# wclock.net
KiCad netlist of a schematic drawn in EAGLE
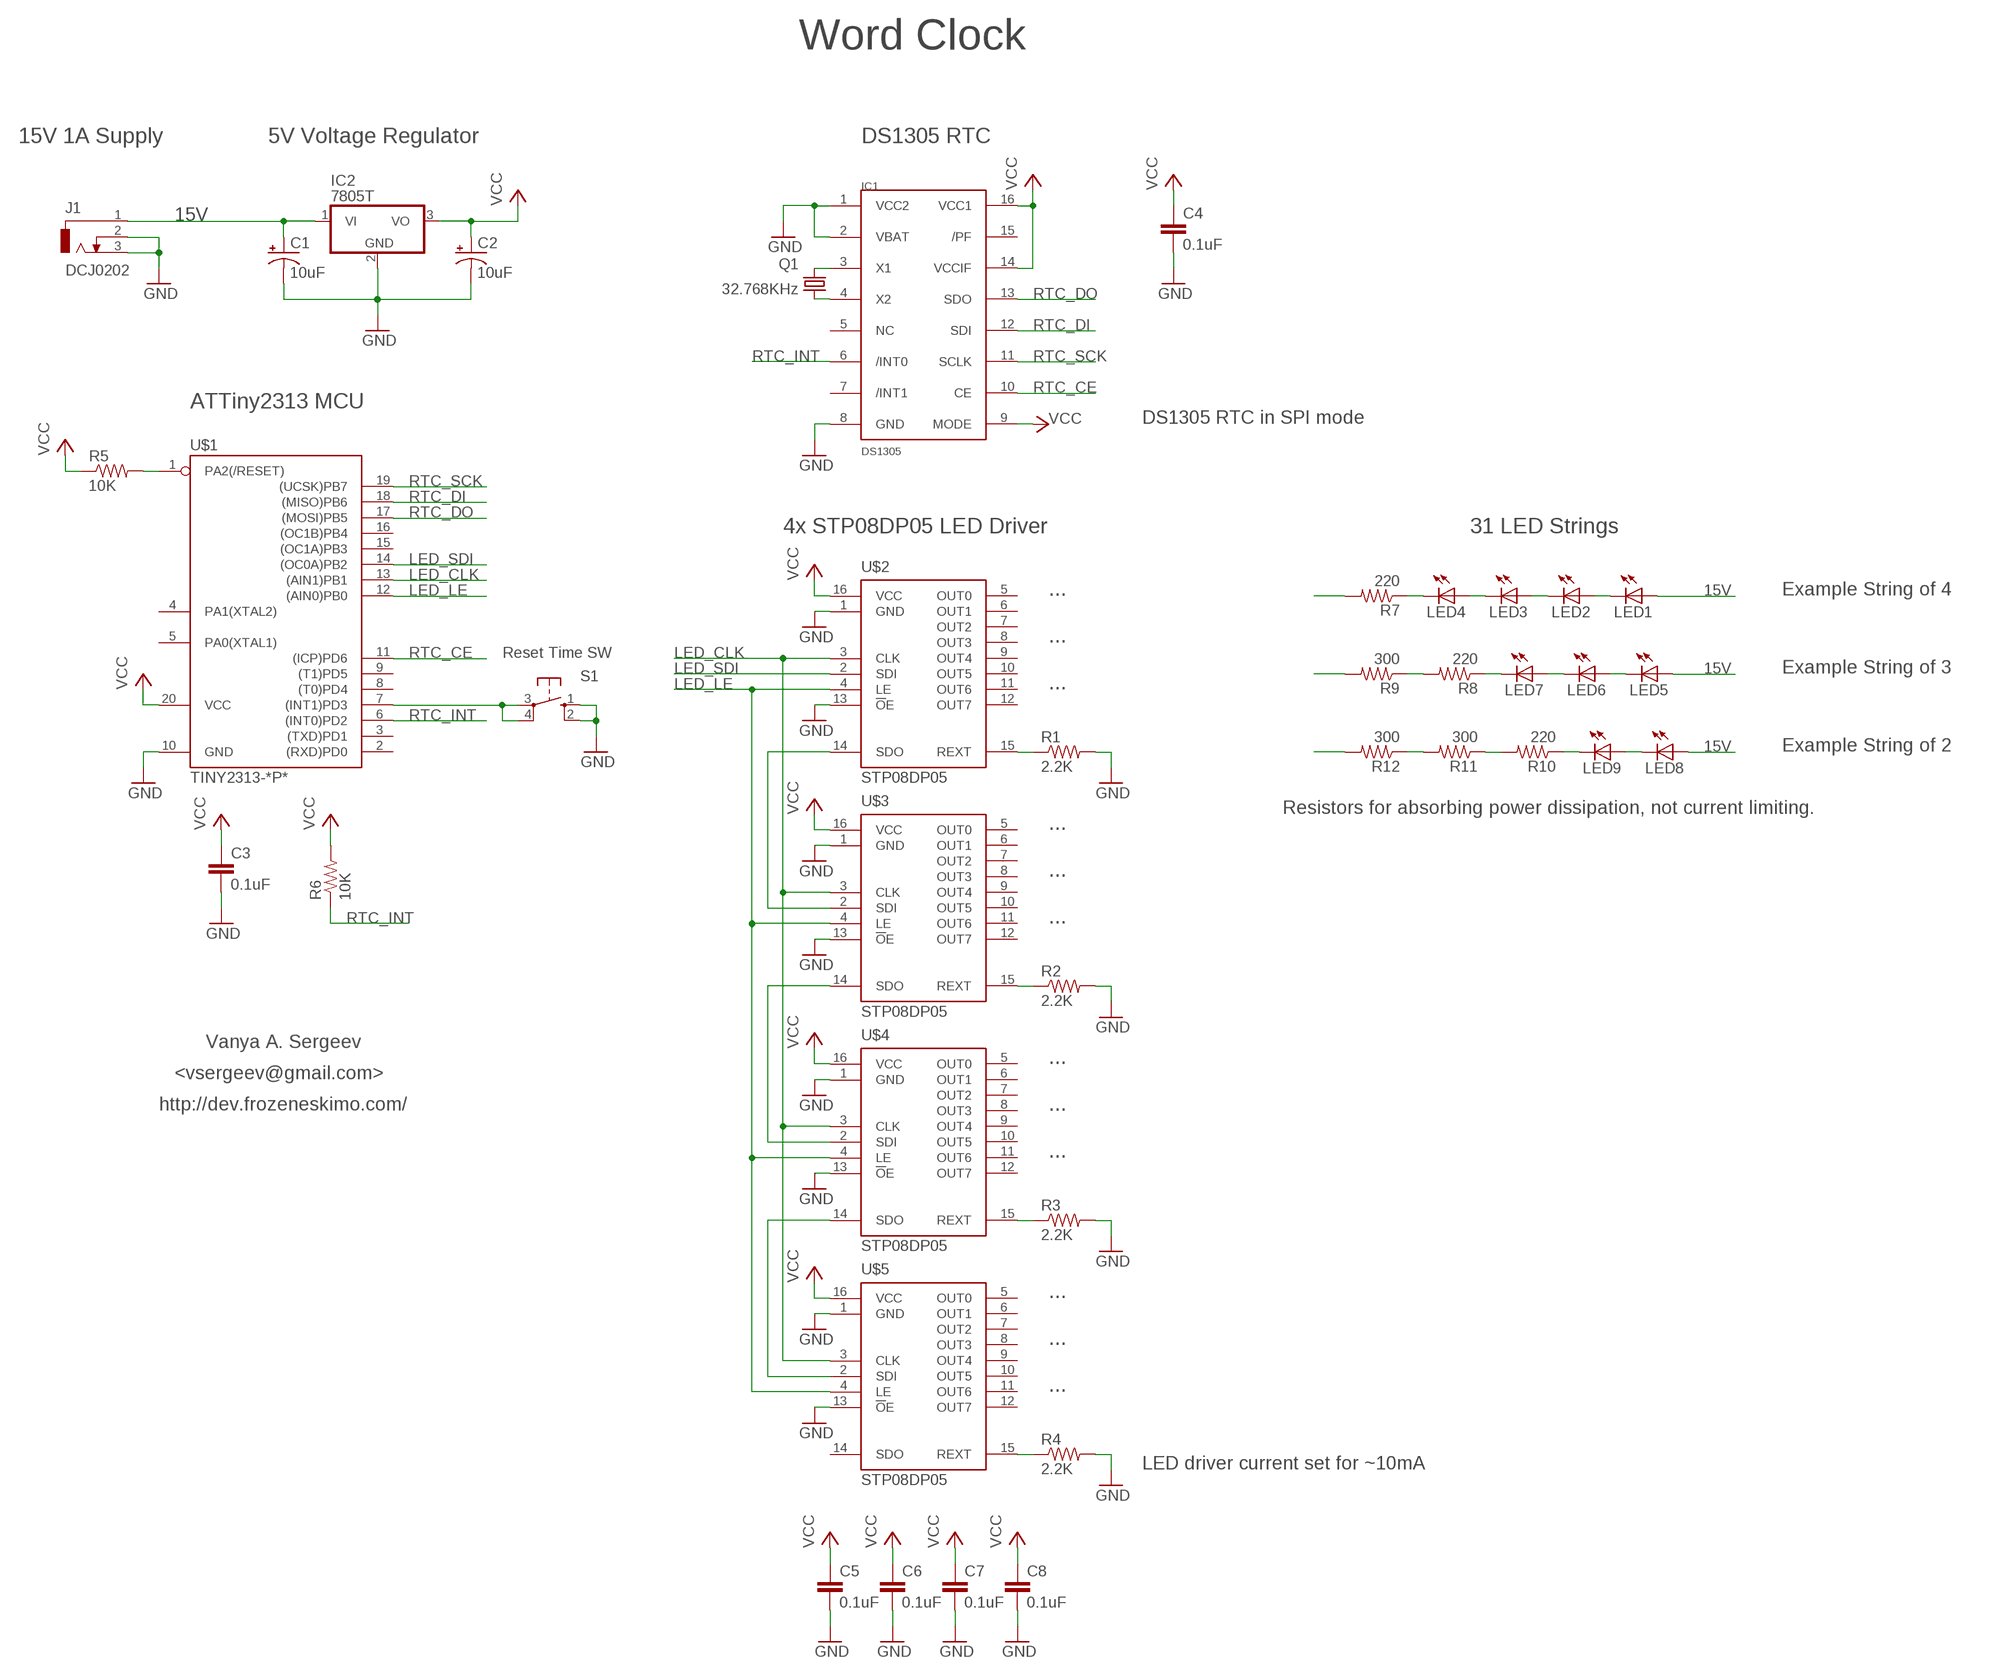
[diagram p0: schematic, sheet 1]

(export (version "E")
  (design (tool "Eeschema 10.0.6"))
  (components
    (comp (ref "C1")
      (value "10uF")
      (footprint "eagle-import:E2,5-5")
      (libsource (lib "eagle-import") (part "CPOL-USE2.5-5"))
    )
    (comp (ref "C2")
      (value "10uF")
      (footprint "eagle-import:E2,5-5")
      (libsource (lib "eagle-import") (part "CPOL-USE2.5-5"))
    )
    (comp (ref "C3")
      (value "0.1uF")
      (footprint "eagle-import:C025-025X050")
      (libsource (lib "eagle-import") (part "C-EU025-025X050"))
    )
    (comp (ref "C4")
      (value "0.1uF")
      (footprint "eagle-import:C025-025X050")
      (libsource (lib "eagle-import") (part "C-EU025-025X050"))
    )
    (comp (ref "C5")
      (value "0.1uF")
      (footprint "eagle-import:C025-025X050")
      (libsource (lib "eagle-import") (part "C-EU025-025X050"))
    )
    (comp (ref "C6")
      (value "0.1uF")
      (footprint "eagle-import:C025-025X050")
      (libsource (lib "eagle-import") (part "C-EU025-025X050"))
    )
    (comp (ref "C7")
      (value "0.1uF")
      (footprint "eagle-import:C025-025X050")
      (libsource (lib "eagle-import") (part "C-EU025-025X050"))
    )
    (comp (ref "C8")
      (value "0.1uF")
      (footprint "eagle-import:C025-025X050")
      (libsource (lib "eagle-import") (part "C-EU025-025X050"))
    )
    (comp (ref "IC1")
      (value "DS1305")
      (footprint "eagle-import:DIL16")
      (libsource (lib "eagle-import") (part "DS1305"))
    )
    (comp (ref "IC2")
      (value "7805T")
      (footprint "eagle-import:TO220H")
      (libsource (lib "eagle-import") (part "78T05"))
    )
    (comp (ref "J1")
      (value "DCJ0202")
      (footprint "eagle-import:DCJ0202")
      (libsource (lib "eagle-import") (part "DCJ0202"))
    )
    (comp (ref "LED1")
      (value "LED5MM")
      (footprint "eagle-import:LED5MM")
      (libsource (lib "eagle-import") (part "LED5MM"))
    )
    (comp (ref "LED2")
      (value "LED5MM")
      (footprint "eagle-import:LED5MM")
      (libsource (lib "eagle-import") (part "LED5MM"))
    )
    (comp (ref "LED3")
      (value "LED5MM")
      (footprint "eagle-import:LED5MM")
      (libsource (lib "eagle-import") (part "LED5MM"))
    )
    (comp (ref "LED4")
      (value "LED5MM")
      (footprint "eagle-import:LED5MM")
      (libsource (lib "eagle-import") (part "LED5MM"))
    )
    (comp (ref "LED5")
      (value "LED5MM")
      (footprint "eagle-import:LED5MM")
      (libsource (lib "eagle-import") (part "LED5MM"))
    )
    (comp (ref "LED6")
      (value "LED5MM")
      (footprint "eagle-import:LED5MM")
      (libsource (lib "eagle-import") (part "LED5MM"))
    )
    (comp (ref "LED7")
      (value "LED5MM")
      (footprint "eagle-import:LED5MM")
      (libsource (lib "eagle-import") (part "LED5MM"))
    )
    (comp (ref "LED8")
      (value "LED5MM")
      (footprint "eagle-import:LED5MM")
      (libsource (lib "eagle-import") (part "LED5MM"))
    )
    (comp (ref "LED9")
      (value "LED5MM")
      (footprint "eagle-import:LED5MM")
      (libsource (lib "eagle-import") (part "LED5MM"))
    )
    (comp (ref "Q1")
      (value "32.768KHz")
      (footprint "eagle-import:TC26V")
      (libsource (lib "eagle-import") (part "CRYSTALTC26V"))
    )
    (comp (ref "R1")
      (value "2.2K")
      (footprint "eagle-import:0207_10")
      (libsource (lib "eagle-import") (part "R-US_0207/10"))
    )
    (comp (ref "R2")
      (value "2.2K")
      (footprint "eagle-import:0207_10")
      (libsource (lib "eagle-import") (part "R-US_0207/10"))
    )
    (comp (ref "R3")
      (value "2.2K")
      (footprint "eagle-import:0207_10")
      (libsource (lib "eagle-import") (part "R-US_0207/10"))
    )
    (comp (ref "R4")
      (value "2.2K")
      (footprint "eagle-import:0207_10")
      (libsource (lib "eagle-import") (part "R-US_0207/10"))
    )
    (comp (ref "R5")
      (value "10K")
      (footprint "eagle-import:0207_10")
      (libsource (lib "eagle-import") (part "R-US_0207/10"))
    )
    (comp (ref "R6")
      (value "10K")
      (footprint "eagle-import:0207_10")
      (libsource (lib "eagle-import") (part "R-US_0207/10"))
    )
    (comp (ref "R7")
      (value "220")
      (footprint "eagle-import:0207_10")
      (libsource (lib "eagle-import") (part "R-US_0207/10"))
    )
    (comp (ref "R8")
      (value "220")
      (footprint "eagle-import:0207_10")
      (libsource (lib "eagle-import") (part "R-US_0207/10"))
    )
    (comp (ref "R9")
      (value "300")
      (footprint "eagle-import:0207_10")
      (libsource (lib "eagle-import") (part "R-US_0207/10"))
    )
    (comp (ref "R10")
      (value "220")
      (footprint "eagle-import:0207_10")
      (libsource (lib "eagle-import") (part "R-US_0207/10"))
    )
    (comp (ref "R11")
      (value "300")
      (footprint "eagle-import:0207_10")
      (libsource (lib "eagle-import") (part "R-US_0207/10"))
    )
    (comp (ref "R12")
      (value "300")
      (footprint "eagle-import:0207_10")
      (libsource (lib "eagle-import") (part "R-US_0207/10"))
    )
    (comp (ref "S1")
      (value "10-XX")
      (footprint "eagle-import:B3F-10XX")
      (fields (field (name "MPN") "B3F-1000"))
      (libsource (lib "eagle-import") (part "10-XX"))
    )
    (comp (ref "U$1")
      (value "TINY2313-*P*")
      (footprint "eagle-import:DIL20")
      (libsource (lib "eagle-import") (part "TINY2313-P"))
    )
    (comp (ref "U$2")
      (value "STP08DP05")
      (footprint "eagle-import:DIL16")
      (libsource (lib "eagle-import") (part "STP08DP05"))
    )
    (comp (ref "U$3")
      (value "STP08DP05")
      (footprint "eagle-import:DIL16")
      (libsource (lib "eagle-import") (part "STP08DP05"))
    )
    (comp (ref "U$4")
      (value "STP08DP05")
      (footprint "eagle-import:DIL16")
      (libsource (lib "eagle-import") (part "STP08DP05"))
    )
    (comp (ref "U$5")
      (value "STP08DP05")
      (footprint "eagle-import:DIL16")
      (libsource (lib "eagle-import") (part "STP08DP05"))
    )
  )
  (nets
    (net (code "1") (name "/15V") (class "Default")
      (node (ref "C1") (pin "+") (pinfunction "+_+") (pintype "passive"))
      (node (ref "IC2") (pin "1") (pinfunction "VI_1") (pintype "input"))
      (node (ref "J1") (pin "1") (pinfunction "1_1") (pintype "passive"))
      (node (ref "LED1") (pin "A") (pinfunction "A_A") (pintype "passive"))
      (node (ref "LED5") (pin "A") (pinfunction "A_A") (pintype "passive"))
      (node (ref "LED8") (pin "A") (pinfunction "A_A") (pintype "passive"))
    )
    (net (code "2") (name "/LED_CLK") (class "Default")
      (node (ref "U$1") (pin "13") (pinfunction "(AIN1)PB1_13") (pintype "bidirectional"))
      (node (ref "U$2") (pin "3") (pinfunction "CLK_3") (pintype "bidirectional"))
      (node (ref "U$3") (pin "3") (pinfunction "CLK_3") (pintype "bidirectional"))
      (node (ref "U$4") (pin "3") (pinfunction "CLK_3") (pintype "bidirectional"))
      (node (ref "U$5") (pin "3") (pinfunction "CLK_3") (pintype "bidirectional"))
    )
    (net (code "3") (name "/LED_LE") (class "Default")
      (node (ref "U$1") (pin "12") (pinfunction "(AIN0)PB0_12") (pintype "bidirectional"))
      (node (ref "U$2") (pin "4") (pinfunction "LE_4") (pintype "bidirectional"))
      (node (ref "U$3") (pin "4") (pinfunction "LE_4") (pintype "bidirectional"))
      (node (ref "U$4") (pin "4") (pinfunction "LE_4") (pintype "bidirectional"))
      (node (ref "U$5") (pin "4") (pinfunction "LE_4") (pintype "bidirectional"))
    )
    (net (code "4") (name "/LED_SDI") (class "Default")
      (node (ref "U$1") (pin "14") (pinfunction "(OC0A)PB2_14") (pintype "bidirectional"))
      (node (ref "U$2") (pin "2") (pinfunction "SDI_2") (pintype "bidirectional"))
    )
    (net (code "5") (name "/RTC_CE") (class "Default")
      (node (ref "IC1") (pin "10") (pinfunction "CE_10") (pintype "input"))
      (node (ref "U$1") (pin "11") (pinfunction "(ICP)PD6_11") (pintype "bidirectional"))
    )
    (net (code "6") (name "/RTC_DI") (class "Default")
      (node (ref "IC1") (pin "12") (pinfunction "SDI_12") (pintype "input"))
      (node (ref "U$1") (pin "18") (pinfunction "(MISO)PB6_18") (pintype "bidirectional"))
    )
    (net (code "7") (name "/RTC_DO") (class "Default")
      (node (ref "IC1") (pin "13") (pinfunction "SDO_13") (pintype "output"))
      (node (ref "U$1") (pin "17") (pinfunction "(MOSI)PB5_17") (pintype "bidirectional"))
    )
    (net (code "8") (name "/RTC_INT") (class "Default")
      (node (ref "IC1") (pin "6") (pinfunction "/INT0_6") (pintype "output"))
      (node (ref "R6") (pin "1") (pinfunction "1_1") (pintype "passive"))
      (node (ref "U$1") (pin "6") (pinfunction "(INT0)PD2_6") (pintype "bidirectional"))
    )
    (net (code "9") (name "/RTC_SCK") (class "Default")
      (node (ref "IC1") (pin "11") (pinfunction "SCLK_11") (pintype "input"))
      (node (ref "U$1") (pin "19") (pinfunction "(UCSK)PB7_19") (pintype "bidirectional"))
    )
    (net (code "10") (name "GND") (class "Default")
      (node (ref "C1") (pin "-") (pinfunction "-_-") (pintype "passive"))
      (node (ref "C2") (pin "-") (pinfunction "-_-") (pintype "passive"))
      (node (ref "C3") (pin "2") (pinfunction "2_2") (pintype "passive"))
      (node (ref "C4") (pin "2") (pinfunction "2_2") (pintype "passive"))
      (node (ref "C5") (pin "2") (pinfunction "2_2") (pintype "passive"))
      (node (ref "C6") (pin "2") (pinfunction "2_2") (pintype "passive"))
      (node (ref "C7") (pin "2") (pinfunction "2_2") (pintype "passive"))
      (node (ref "C8") (pin "2") (pinfunction "2_2") (pintype "passive"))
      (node (ref "IC1") (pin "1") (pinfunction "VCC2_1") (pintype "power_in"))
      (node (ref "IC1") (pin "2") (pinfunction "VBAT_2") (pintype "power_in"))
      (node (ref "IC1") (pin "8") (pinfunction "GND_8") (pintype "power_in"))
      (node (ref "IC2") (pin "2") (pinfunction "GND_2") (pintype "passive"))
      (node (ref "J1") (pin "2") (pinfunction "2_2") (pintype "passive"))
      (node (ref "J1") (pin "3") (pinfunction "3_3") (pintype "passive"))
      (node (ref "R1") (pin "2") (pinfunction "2_2") (pintype "passive"))
      (node (ref "R2") (pin "2") (pinfunction "2_2") (pintype "passive"))
      (node (ref "R3") (pin "2") (pinfunction "2_2") (pintype "passive"))
      (node (ref "R4") (pin "2") (pinfunction "2_2") (pintype "passive"))
      (node (ref "S1") (pin "1") (pinfunction "S_1") (pintype "passive"))
      (node (ref "S1") (pin "2") (pinfunction "S1_2") (pintype "passive"))
      (node (ref "U$1") (pin "10") (pinfunction "GND_10") (pintype "power_in"))
      (node (ref "U$2") (pin "1") (pinfunction "GND_1") (pintype "power_in"))
      (node (ref "U$2") (pin "13") (pinfunction "~{O}E_13") (pintype "bidirectional"))
      (node (ref "U$3") (pin "1") (pinfunction "GND_1") (pintype "power_in"))
      (node (ref "U$3") (pin "13") (pinfunction "~{O}E_13") (pintype "bidirectional"))
      (node (ref "U$4") (pin "1") (pinfunction "GND_1") (pintype "power_in"))
      (node (ref "U$4") (pin "13") (pinfunction "~{O}E_13") (pintype "bidirectional"))
      (node (ref "U$5") (pin "1") (pinfunction "GND_1") (pintype "power_in"))
      (node (ref "U$5") (pin "13") (pinfunction "~{O}E_13") (pintype "bidirectional"))
    )
    (net (code "11") (name "Net-(IC1-X1)") (class "Default")
      (node (ref "IC1") (pin "3") (pinfunction "X1_3") (pintype "input"))
      (node (ref "Q1") (pin "2") (pinfunction "2_2") (pintype "passive"))
    )
    (net (code "12") (name "Net-(IC1-X2)") (class "Default")
      (node (ref "IC1") (pin "4") (pinfunction "X2_4") (pintype "output"))
      (node (ref "Q1") (pin "1") (pinfunction "1_1") (pintype "passive"))
    )
    (net (code "13") (name "Net-(LED1-C)") (class "Default")
      (node (ref "LED1") (pin "K") (pinfunction "C_K") (pintype "passive"))
      (node (ref "LED2") (pin "A") (pinfunction "A_A") (pintype "passive"))
    )
    (net (code "14") (name "Net-(LED2-C)") (class "Default")
      (node (ref "LED2") (pin "K") (pinfunction "C_K") (pintype "passive"))
      (node (ref "LED3") (pin "A") (pinfunction "A_A") (pintype "passive"))
    )
    (net (code "15") (name "Net-(LED3-C)") (class "Default")
      (node (ref "LED3") (pin "K") (pinfunction "C_K") (pintype "passive"))
      (node (ref "LED4") (pin "A") (pinfunction "A_A") (pintype "passive"))
    )
    (net (code "16") (name "Net-(LED4-C)") (class "Default")
      (node (ref "LED4") (pin "K") (pinfunction "C_K") (pintype "passive"))
      (node (ref "R7") (pin "1") (pinfunction "1_1") (pintype "passive"))
    )
    (net (code "17") (name "Net-(LED5-C)") (class "Default")
      (node (ref "LED5") (pin "K") (pinfunction "C_K") (pintype "passive"))
      (node (ref "LED6") (pin "A") (pinfunction "A_A") (pintype "passive"))
    )
    (net (code "18") (name "Net-(LED6-C)") (class "Default")
      (node (ref "LED6") (pin "K") (pinfunction "C_K") (pintype "passive"))
      (node (ref "LED7") (pin "A") (pinfunction "A_A") (pintype "passive"))
    )
    (net (code "19") (name "Net-(LED7-C)") (class "Default")
      (node (ref "LED7") (pin "K") (pinfunction "C_K") (pintype "passive"))
      (node (ref "R8") (pin "1") (pinfunction "1_1") (pintype "passive"))
    )
    (net (code "20") (name "Net-(LED8-C)") (class "Default")
      (node (ref "LED8") (pin "K") (pinfunction "C_K") (pintype "passive"))
      (node (ref "LED9") (pin "A") (pinfunction "A_A") (pintype "passive"))
    )
    (net (code "21") (name "Net-(LED9-C)") (class "Default")
      (node (ref "LED9") (pin "K") (pinfunction "C_K") (pintype "passive"))
      (node (ref "R10") (pin "1") (pinfunction "1_1") (pintype "passive"))
    )
    (net (code "22") (name "Net-(R8-Pad2)") (class "Default")
      (node (ref "R8") (pin "2") (pinfunction "2_2") (pintype "passive"))
      (node (ref "R9") (pin "1") (pinfunction "1_1") (pintype "passive"))
    )
    (net (code "23") (name "Net-(R10-Pad2)") (class "Default")
      (node (ref "R10") (pin "2") (pinfunction "2_2") (pintype "passive"))
      (node (ref "R11") (pin "1") (pinfunction "1_1") (pintype "passive"))
    )
    (net (code "24") (name "Net-(R11-Pad2)") (class "Default")
      (node (ref "R11") (pin "2") (pinfunction "2_2") (pintype "passive"))
      (node (ref "R12") (pin "1") (pinfunction "1_1") (pintype "passive"))
    )
    (net (code "25") (name "Net-(S1-P)") (class "Default")
      (node (ref "S1") (pin "3") (pinfunction "P_3") (pintype "passive"))
      (node (ref "S1") (pin "4") (pinfunction "P1_4") (pintype "passive"))
      (node (ref "U$1") (pin "7") (pinfunction "(INT1)PD3_7") (pintype "bidirectional"))
    )
    (net (code "26") (name "Net-(U$1-PA2({slash}RESET))") (class "Default")
      (node (ref "R5") (pin "2") (pinfunction "2_2") (pintype "passive"))
      (node (ref "U$1") (pin "1") (pinfunction "PA2(/RESET)_1") (pintype "input"))
    )
    (net (code "27") (name "Net-(U$2-REXT)") (class "Default")
      (node (ref "R1") (pin "1") (pinfunction "1_1") (pintype "passive"))
      (node (ref "U$2") (pin "15") (pinfunction "REXT_15") (pintype "passive"))
    )
    (net (code "28") (name "Net-(U$2-SDO)") (class "Default")
      (node (ref "U$2") (pin "14") (pinfunction "SDO_14") (pintype "bidirectional"))
      (node (ref "U$3") (pin "2") (pinfunction "SDI_2") (pintype "bidirectional"))
    )
    (net (code "29") (name "Net-(U$3-REXT)") (class "Default")
      (node (ref "R2") (pin "1") (pinfunction "1_1") (pintype "passive"))
      (node (ref "U$3") (pin "15") (pinfunction "REXT_15") (pintype "passive"))
    )
    (net (code "30") (name "Net-(U$3-SDO)") (class "Default")
      (node (ref "U$3") (pin "14") (pinfunction "SDO_14") (pintype "bidirectional"))
      (node (ref "U$4") (pin "2") (pinfunction "SDI_2") (pintype "bidirectional"))
    )
    (net (code "31") (name "Net-(U$4-REXT)") (class "Default")
      (node (ref "R3") (pin "1") (pinfunction "1_1") (pintype "passive"))
      (node (ref "U$4") (pin "15") (pinfunction "REXT_15") (pintype "passive"))
    )
    (net (code "32") (name "Net-(U$4-SDO)") (class "Default")
      (node (ref "U$4") (pin "14") (pinfunction "SDO_14") (pintype "bidirectional"))
      (node (ref "U$5") (pin "2") (pinfunction "SDI_2") (pintype "bidirectional"))
    )
    (net (code "33") (name "Net-(U$5-REXT)") (class "Default")
      (node (ref "R4") (pin "1") (pinfunction "1_1") (pintype "passive"))
      (node (ref "U$5") (pin "15") (pinfunction "REXT_15") (pintype "passive"))
    )
    (net (code "34") (name "VCC") (class "Default")
      (node (ref "C2") (pin "+") (pinfunction "+_+") (pintype "passive"))
      (node (ref "C3") (pin "1") (pinfunction "1_1") (pintype "passive"))
      (node (ref "C4") (pin "1") (pinfunction "1_1") (pintype "passive"))
      (node (ref "C5") (pin "1") (pinfunction "1_1") (pintype "passive"))
      (node (ref "C6") (pin "1") (pinfunction "1_1") (pintype "passive"))
      (node (ref "C7") (pin "1") (pinfunction "1_1") (pintype "passive"))
      (node (ref "C8") (pin "1") (pinfunction "1_1") (pintype "passive"))
      (node (ref "IC1") (pin "14") (pinfunction "VCCIF_14") (pintype "power_in"))
      (node (ref "IC1") (pin "16") (pinfunction "VCC1_16") (pintype "power_in"))
      (node (ref "IC1") (pin "9") (pinfunction "MODE_9") (pintype "input"))
      (node (ref "IC2") (pin "3") (pinfunction "VO_3") (pintype "passive"))
      (node (ref "R5") (pin "1") (pinfunction "1_1") (pintype "passive"))
      (node (ref "R6") (pin "2") (pinfunction "2_2") (pintype "passive"))
      (node (ref "U$1") (pin "20") (pinfunction "VCC_20") (pintype "power_in"))
      (node (ref "U$2") (pin "16") (pinfunction "VCC_16") (pintype "power_in"))
      (node (ref "U$3") (pin "16") (pinfunction "VCC_16") (pintype "power_in"))
      (node (ref "U$4") (pin "16") (pinfunction "VCC_16") (pintype "power_in"))
      (node (ref "U$5") (pin "16") (pinfunction "VCC_16") (pintype "power_in"))
    )
    (net (code "35") (name "unconnected-(IC1-NC-Pad5)") (class "Default")
      (node (ref "IC1") (pin "5") (pinfunction "NC_5") (pintype "bidirectional"))
    )
    (net (code "36") (name "unconnected-(IC1-{slash}INT1-Pad7)") (class "Default")
      (node (ref "IC1") (pin "7") (pinfunction "/INT1_7") (pintype "output"))
    )
    (net (code "37") (name "unconnected-(IC1-{slash}PF-Pad15)") (class "Default")
      (node (ref "IC1") (pin "15") (pinfunction "/PF_15") (pintype "output"))
    )
    (net (code "38") (name "unconnected-(R7-Pad2)") (class "Default")
      (node (ref "R7") (pin "2") (pinfunction "2_2") (pintype "passive"))
    )
    (net (code "39") (name "unconnected-(R9-Pad2)") (class "Default")
      (node (ref "R9") (pin "2") (pinfunction "2_2") (pintype "passive"))
    )
    (net (code "40") (name "unconnected-(R12-Pad2)") (class "Default")
      (node (ref "R12") (pin "2") (pinfunction "2_2") (pintype "passive"))
    )
    (net (code "41") (name "unconnected-(U$1-(OC1A)PB3-Pad15)") (class "Default")
      (node (ref "U$1") (pin "15") (pinfunction "(OC1A)PB3_15") (pintype "bidirectional"))
    )
    (net (code "42") (name "unconnected-(U$1-(OC1B)PB4-Pad16)") (class "Default")
      (node (ref "U$1") (pin "16") (pinfunction "(OC1B)PB4_16") (pintype "bidirectional"))
    )
    (net (code "43") (name "unconnected-(U$1-(RXD)PD0-Pad2)") (class "Default")
      (node (ref "U$1") (pin "2") (pinfunction "(RXD)PD0_2") (pintype "bidirectional"))
    )
    (net (code "44") (name "unconnected-(U$1-(T0)PD4-Pad8)") (class "Default")
      (node (ref "U$1") (pin "8") (pinfunction "(T0)PD4_8") (pintype "bidirectional"))
    )
    (net (code "45") (name "unconnected-(U$1-(T1)PD5-Pad9)") (class "Default")
      (node (ref "U$1") (pin "9") (pinfunction "(T1)PD5_9") (pintype "bidirectional"))
    )
    (net (code "46") (name "unconnected-(U$1-(TXD)PD1-Pad3)") (class "Default")
      (node (ref "U$1") (pin "3") (pinfunction "(TXD)PD1_3") (pintype "bidirectional"))
    )
    (net (code "47") (name "unconnected-(U$1-PA0(XTAL1)-Pad5)") (class "Default")
      (node (ref "U$1") (pin "5") (pinfunction "PA0(XTAL1)_5") (pintype "bidirectional"))
    )
    (net (code "48") (name "unconnected-(U$1-PA1(XTAL2)-Pad4)") (class "Default")
      (node (ref "U$1") (pin "4") (pinfunction "PA1(XTAL2)_4") (pintype "bidirectional"))
    )
    (net (code "49") (name "unconnected-(U$2-OUT0-Pad5)") (class "Default")
      (node (ref "U$2") (pin "5") (pinfunction "OUT0_5") (pintype "bidirectional"))
    )
    (net (code "50") (name "unconnected-(U$2-OUT1-Pad6)") (class "Default")
      (node (ref "U$2") (pin "6") (pinfunction "OUT1_6") (pintype "bidirectional"))
    )
    (net (code "51") (name "unconnected-(U$2-OUT2-Pad7)") (class "Default")
      (node (ref "U$2") (pin "7") (pinfunction "OUT2_7") (pintype "bidirectional"))
    )
    (net (code "52") (name "unconnected-(U$2-OUT3-Pad8)") (class "Default")
      (node (ref "U$2") (pin "8") (pinfunction "OUT3_8") (pintype "bidirectional"))
    )
    (net (code "53") (name "unconnected-(U$2-OUT4-Pad9)") (class "Default")
      (node (ref "U$2") (pin "9") (pinfunction "OUT4_9") (pintype "bidirectional"))
    )
    (net (code "54") (name "unconnected-(U$2-OUT5-Pad10)") (class "Default")
      (node (ref "U$2") (pin "10") (pinfunction "OUT5_10") (pintype "bidirectional"))
    )
    (net (code "55") (name "unconnected-(U$2-OUT6-Pad11)") (class "Default")
      (node (ref "U$2") (pin "11") (pinfunction "OUT6_11") (pintype "bidirectional"))
    )
    (net (code "56") (name "unconnected-(U$2-OUT7-Pad12)") (class "Default")
      (node (ref "U$2") (pin "12") (pinfunction "OUT7_12") (pintype "bidirectional"))
    )
    (net (code "57") (name "unconnected-(U$3-OUT0-Pad5)") (class "Default")
      (node (ref "U$3") (pin "5") (pinfunction "OUT0_5") (pintype "bidirectional"))
    )
    (net (code "58") (name "unconnected-(U$3-OUT1-Pad6)") (class "Default")
      (node (ref "U$3") (pin "6") (pinfunction "OUT1_6") (pintype "bidirectional"))
    )
    (net (code "59") (name "unconnected-(U$3-OUT2-Pad7)") (class "Default")
      (node (ref "U$3") (pin "7") (pinfunction "OUT2_7") (pintype "bidirectional"))
    )
    (net (code "60") (name "unconnected-(U$3-OUT3-Pad8)") (class "Default")
      (node (ref "U$3") (pin "8") (pinfunction "OUT3_8") (pintype "bidirectional"))
    )
    (net (code "61") (name "unconnected-(U$3-OUT4-Pad9)") (class "Default")
      (node (ref "U$3") (pin "9") (pinfunction "OUT4_9") (pintype "bidirectional"))
    )
    (net (code "62") (name "unconnected-(U$3-OUT5-Pad10)") (class "Default")
      (node (ref "U$3") (pin "10") (pinfunction "OUT5_10") (pintype "bidirectional"))
    )
    (net (code "63") (name "unconnected-(U$3-OUT6-Pad11)") (class "Default")
      (node (ref "U$3") (pin "11") (pinfunction "OUT6_11") (pintype "bidirectional"))
    )
    (net (code "64") (name "unconnected-(U$3-OUT7-Pad12)") (class "Default")
      (node (ref "U$3") (pin "12") (pinfunction "OUT7_12") (pintype "bidirectional"))
    )
    (net (code "65") (name "unconnected-(U$4-OUT0-Pad5)") (class "Default")
      (node (ref "U$4") (pin "5") (pinfunction "OUT0_5") (pintype "bidirectional"))
    )
    (net (code "66") (name "unconnected-(U$4-OUT1-Pad6)") (class "Default")
      (node (ref "U$4") (pin "6") (pinfunction "OUT1_6") (pintype "bidirectional"))
    )
    (net (code "67") (name "unconnected-(U$4-OUT2-Pad7)") (class "Default")
      (node (ref "U$4") (pin "7") (pinfunction "OUT2_7") (pintype "bidirectional"))
    )
    (net (code "68") (name "unconnected-(U$4-OUT3-Pad8)") (class "Default")
      (node (ref "U$4") (pin "8") (pinfunction "OUT3_8") (pintype "bidirectional"))
    )
    (net (code "69") (name "unconnected-(U$4-OUT4-Pad9)") (class "Default")
      (node (ref "U$4") (pin "9") (pinfunction "OUT4_9") (pintype "bidirectional"))
    )
    (net (code "70") (name "unconnected-(U$4-OUT5-Pad10)") (class "Default")
      (node (ref "U$4") (pin "10") (pinfunction "OUT5_10") (pintype "bidirectional"))
    )
    (net (code "71") (name "unconnected-(U$4-OUT6-Pad11)") (class "Default")
      (node (ref "U$4") (pin "11") (pinfunction "OUT6_11") (pintype "bidirectional"))
    )
    (net (code "72") (name "unconnected-(U$4-OUT7-Pad12)") (class "Default")
      (node (ref "U$4") (pin "12") (pinfunction "OUT7_12") (pintype "bidirectional"))
    )
    (net (code "73") (name "unconnected-(U$5-OUT0-Pad5)") (class "Default")
      (node (ref "U$5") (pin "5") (pinfunction "OUT0_5") (pintype "bidirectional"))
    )
    (net (code "74") (name "unconnected-(U$5-OUT1-Pad6)") (class "Default")
      (node (ref "U$5") (pin "6") (pinfunction "OUT1_6") (pintype "bidirectional"))
    )
    (net (code "75") (name "unconnected-(U$5-OUT2-Pad7)") (class "Default")
      (node (ref "U$5") (pin "7") (pinfunction "OUT2_7") (pintype "bidirectional"))
    )
    (net (code "76") (name "unconnected-(U$5-OUT3-Pad8)") (class "Default")
      (node (ref "U$5") (pin "8") (pinfunction "OUT3_8") (pintype "bidirectional"))
    )
    (net (code "77") (name "unconnected-(U$5-OUT4-Pad9)") (class "Default")
      (node (ref "U$5") (pin "9") (pinfunction "OUT4_9") (pintype "bidirectional"))
    )
    (net (code "78") (name "unconnected-(U$5-OUT5-Pad10)") (class "Default")
      (node (ref "U$5") (pin "10") (pinfunction "OUT5_10") (pintype "bidirectional"))
    )
    (net (code "79") (name "unconnected-(U$5-OUT6-Pad11)") (class "Default")
      (node (ref "U$5") (pin "11") (pinfunction "OUT6_11") (pintype "bidirectional"))
    )
    (net (code "80") (name "unconnected-(U$5-OUT7-Pad12)") (class "Default")
      (node (ref "U$5") (pin "12") (pinfunction "OUT7_12") (pintype "bidirectional"))
    )
    (net (code "81") (name "unconnected-(U$5-SDO-Pad14)") (class "Default")
      (node (ref "U$5") (pin "14") (pinfunction "SDO_14") (pintype "bidirectional"))
    )
  )
)
